# thermo-stats.net
KiCad netlist of a schematic drawn in EasyEDA
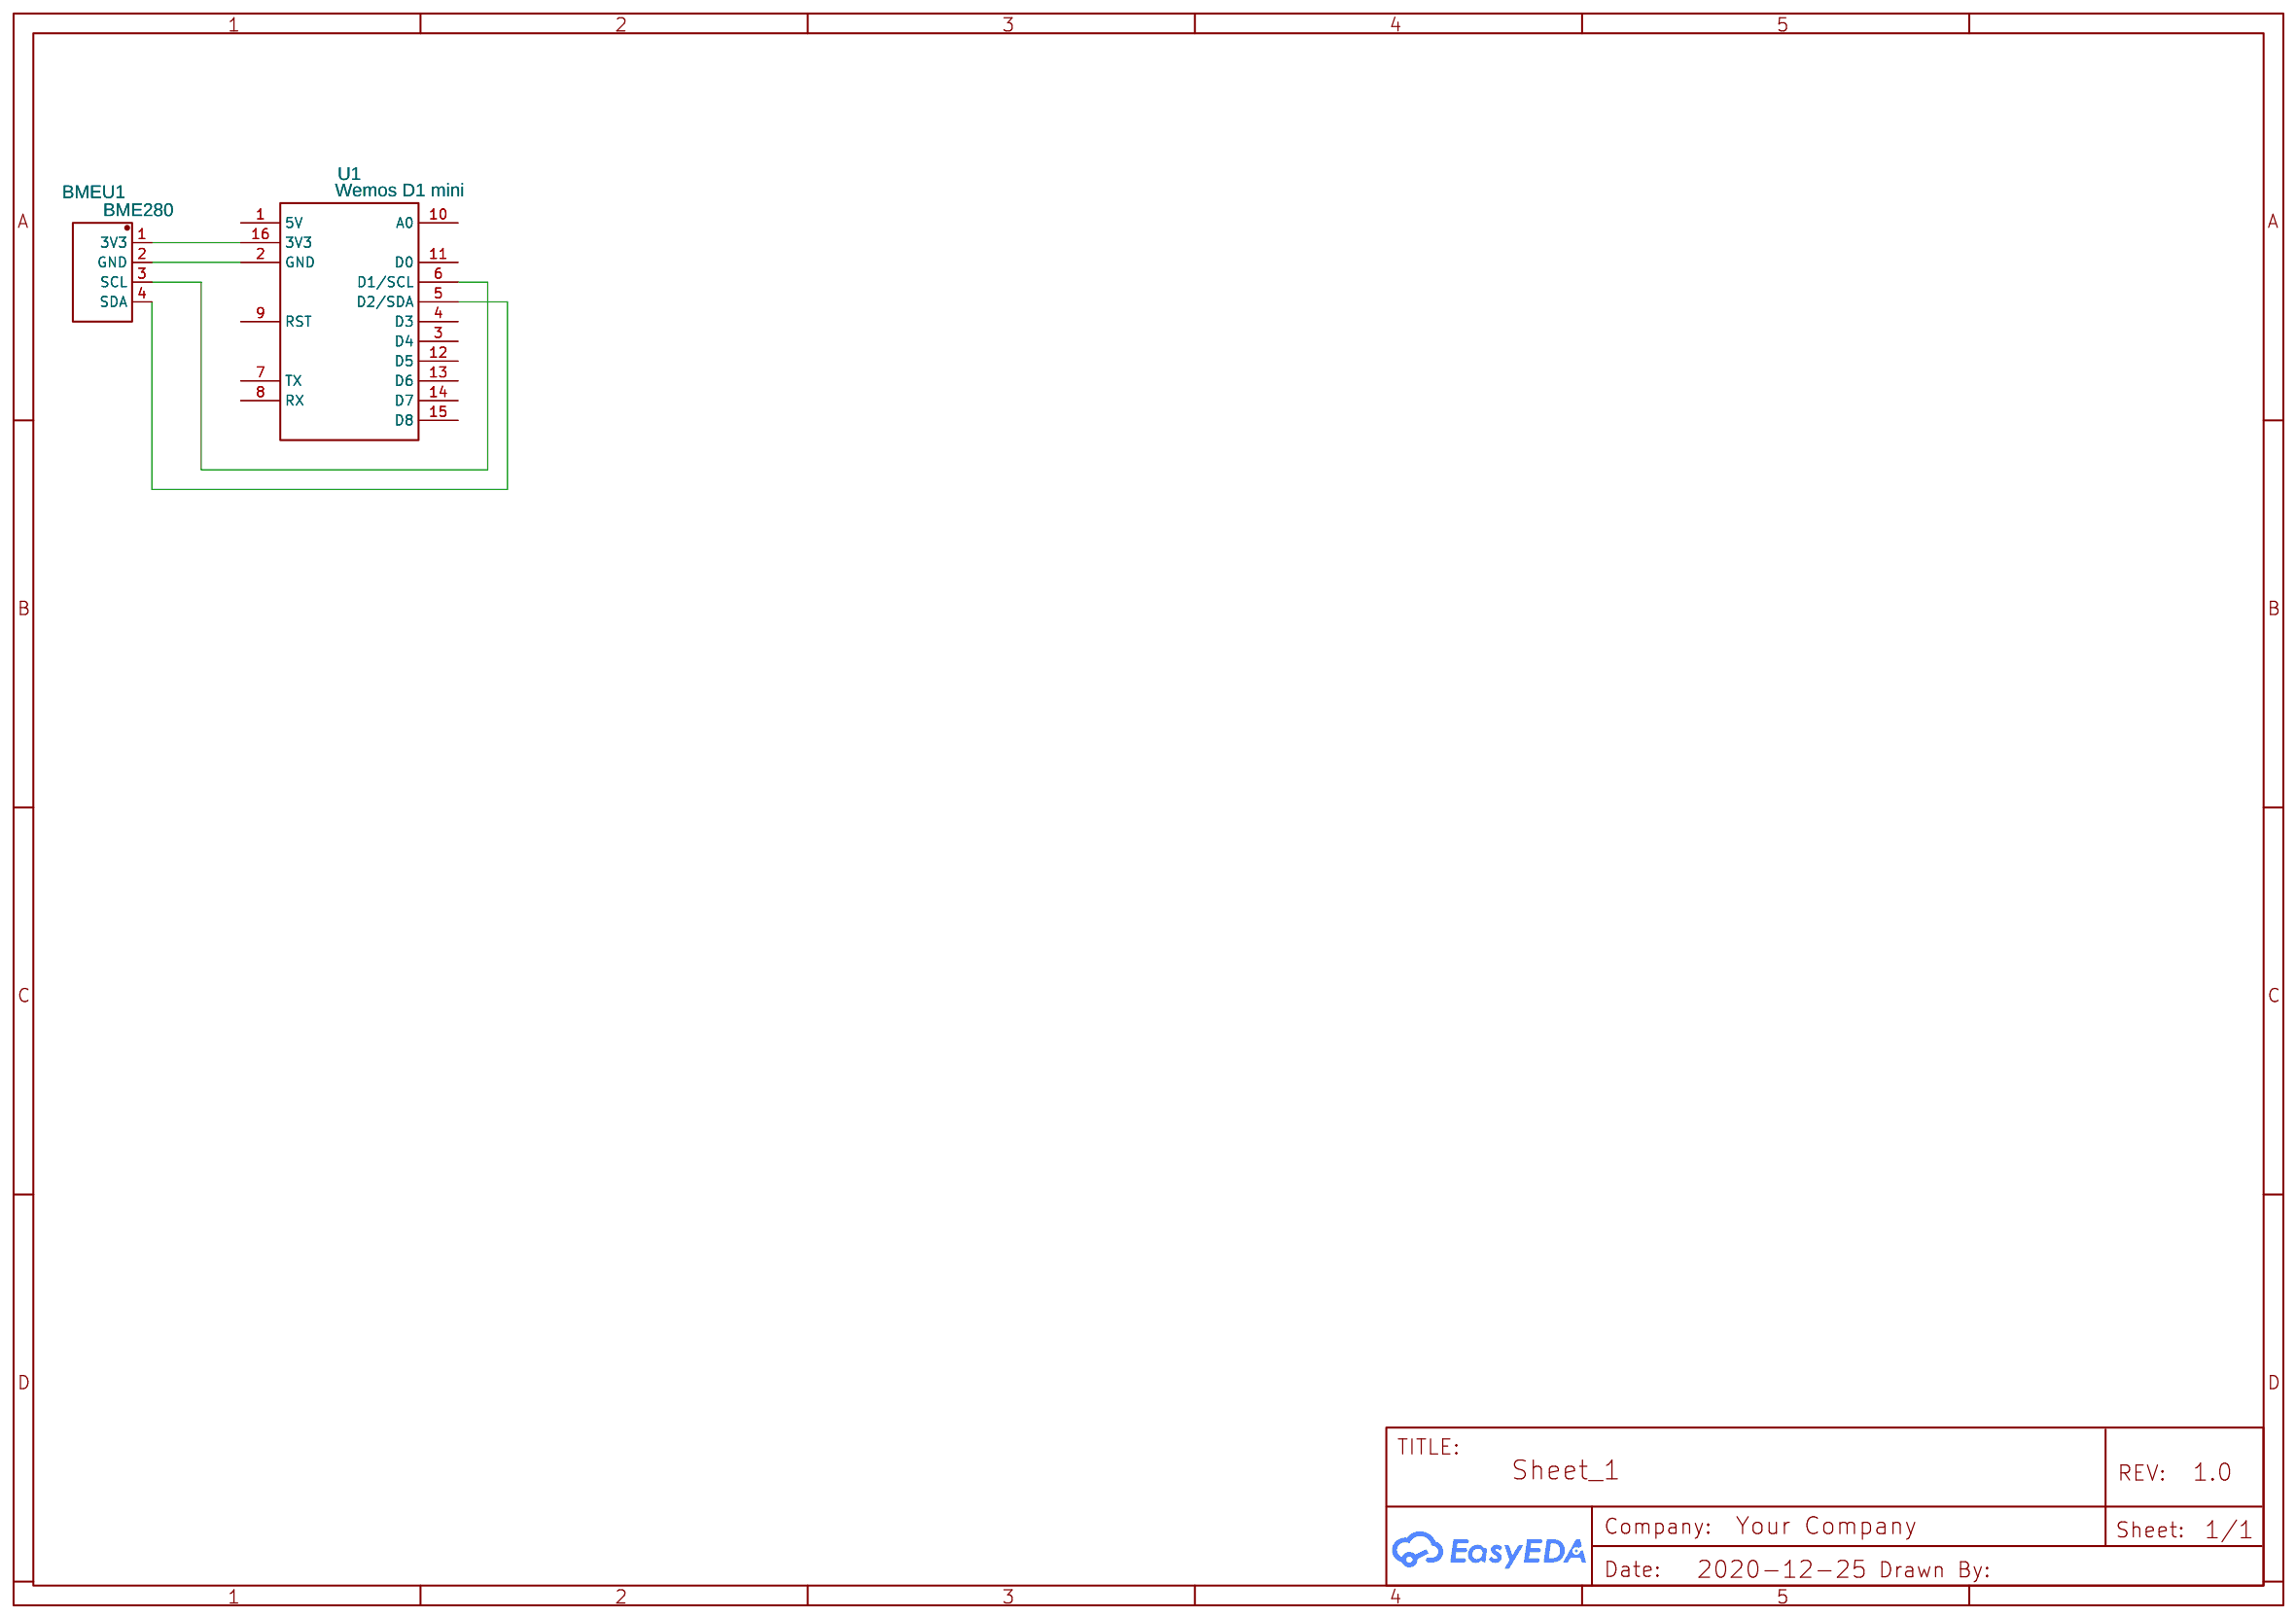
[diagram p0: schematic sheet]

(export (version "E")
  (design (tool "Eeschema 10.0.6"))
  (components
    (comp (ref "BMEU1")
      (value "BME280")
      (fields (field (name "BOM_Manufacturer Part") "?"))
      (libsource (lib "") (part "Unknown_40_-670"))
    )
    (comp (ref "U1") (value "Wemos D1 mini") (libsource (lib "") (part "Wemos D1 mini")))
  )
  (nets
    (net (code "1") (name "Net-(BMEU1-3V3)") (class "Default")
      (node (ref "BMEU1") (pin "1") (pinfunction "3V3_1") (pintype "unspecified"))
      (node (ref "U1") (pin "16") (pinfunction "3V3_16") (pintype "unspecified"))
    )
    (net (code "2") (name "Net-(BMEU1-GND)") (class "Default")
      (node (ref "BMEU1") (pin "2") (pinfunction "GND_2") (pintype "unspecified"))
      (node (ref "U1") (pin "2") (pinfunction "GND_2") (pintype "unspecified"))
    )
    (net (code "3") (name "Net-(BMEU1-SCL)") (class "Default")
      (node (ref "BMEU1") (pin "3") (pinfunction "SCL_3") (pintype "unspecified"))
      (node (ref "U1") (pin "6") (pinfunction "D1/SCL_6") (pintype "unspecified"))
    )
    (net (code "4") (name "Net-(BMEU1-SDA)") (class "Default")
      (node (ref "BMEU1") (pin "4") (pinfunction "SDA_4") (pintype "unspecified"))
      (node (ref "U1") (pin "5") (pinfunction "D2/SDA_5") (pintype "unspecified"))
    )
    (net (code "5") (name "unconnected-(U1-5V-Pad1)") (class "Default")
      (node (ref "U1") (pin "1") (pinfunction "5V_1") (pintype "unspecified"))
    )
    (net (code "6") (name "unconnected-(U1-A0-Pad10)") (class "Default")
      (node (ref "U1") (pin "10") (pinfunction "A0_10") (pintype "unspecified"))
    )
    (net (code "7") (name "unconnected-(U1-D0-Pad11)") (class "Default")
      (node (ref "U1") (pin "11") (pinfunction "D0_11") (pintype "unspecified"))
    )
    (net (code "8") (name "unconnected-(U1-D3-Pad4)") (class "Default")
      (node (ref "U1") (pin "4") (pinfunction "D3_4") (pintype "unspecified"))
    )
    (net (code "9") (name "unconnected-(U1-D4-Pad3)") (class "Default")
      (node (ref "U1") (pin "3") (pinfunction "D4_3") (pintype "unspecified"))
    )
    (net (code "10") (name "unconnected-(U1-D5-Pad12)") (class "Default")
      (node (ref "U1") (pin "12") (pinfunction "D5_12") (pintype "unspecified"))
    )
    (net (code "11") (name "unconnected-(U1-D6-Pad13)") (class "Default")
      (node (ref "U1") (pin "13") (pinfunction "D6_13") (pintype "unspecified"))
    )
    (net (code "12") (name "unconnected-(U1-D7-Pad14)") (class "Default")
      (node (ref "U1") (pin "14") (pinfunction "D7_14") (pintype "unspecified"))
    )
    (net (code "13") (name "unconnected-(U1-D8-Pad15)") (class "Default")
      (node (ref "U1") (pin "15") (pinfunction "D8_15") (pintype "unspecified"))
    )
    (net (code "14") (name "unconnected-(U1-RST-Pad9)") (class "Default")
      (node (ref "U1") (pin "9") (pinfunction "RST_9") (pintype "unspecified"))
    )
    (net (code "15") (name "unconnected-(U1-RX-Pad8)") (class "Default")
      (node (ref "U1") (pin "8") (pinfunction "RX_8") (pintype "unspecified"))
    )
    (net (code "16") (name "unconnected-(U1-TX-Pad7)") (class "Default")
      (node (ref "U1") (pin "7") (pinfunction "TX_7") (pintype "unspecified"))
    )
  )
)
